# TopPannel.net
KiCad netlist of a schematic drawn in Altium Designer
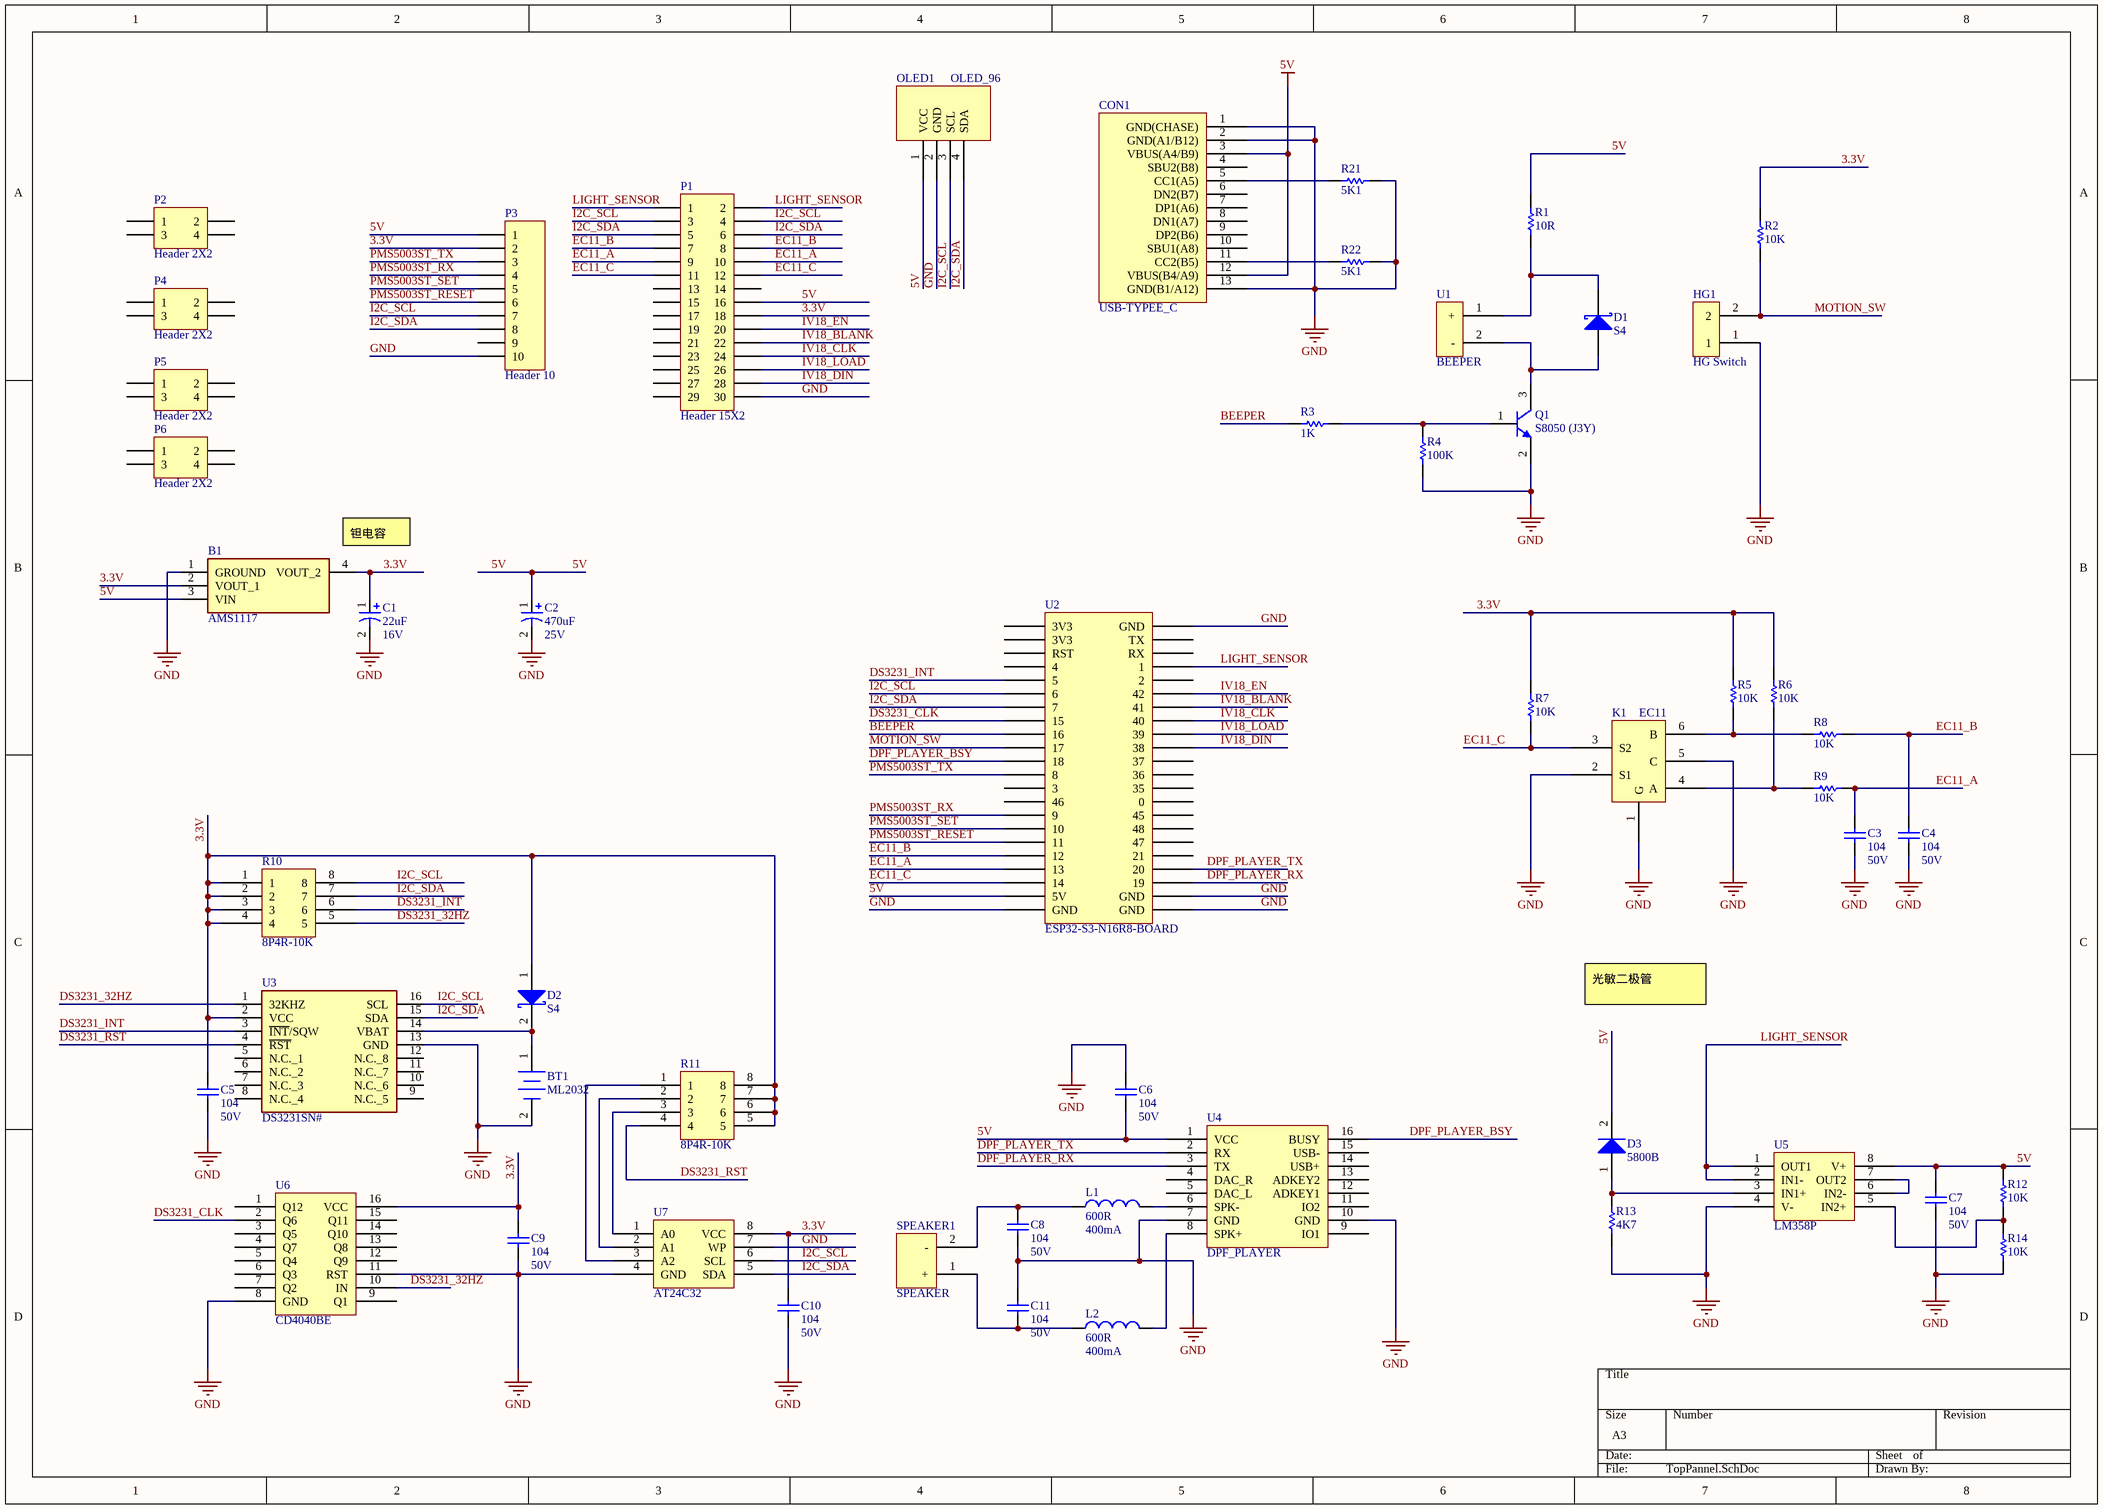
[diagram p0: TopPannel.SchDoc]

(export (version "E")
  (design (tool "Eeschema 10.0.6"))
  (components
    (comp (ref "B1")
      (value "AMS1117")
      (footprint "SOT229P700X180-4N")
      (description "1117")
      (libsource (lib "NeoIVClock") (part "AMS1117"))
    )
    (comp (ref "BT1")
      (value "ML2032")
      (footprint "NeoIVClock:BAT2025-2032-L")
      (description "Multicell Battery")
      (fields (field (name "PUBLISHER") "Altium Limited"))
      (libsource (lib "Miscellaneous Devices") (part "Battery"))
    )
    (comp (ref "C1")
      (value "16V")
      (footprint "NeoIVClock:TC3216-1206")
      (description "Polarized Capacitor (Radial)")
      (fields (field (name "ALTIUM_VALUE") "22uF") (field (name "PUBLISHER") "Altium Limited"))
      (libsource (lib "Miscellaneous Devices") (part "Cap Pol1"))
    )
    (comp (ref "C2")
      (value "25V")
      (footprint "NeoIVClock:SMD-EC-F10")
      (description "Polarized Capacitor (Radial)")
      (fields (field (name "ALTIUM_VALUE") "470uF") (field (name "PUBLISHER") "Altium Limited"))
      (libsource (lib "Miscellaneous Devices") (part "Cap Pol1"))
    )
    (comp (ref "C3")
      (value "50V")
      (footprint "NeoIVClock:CAPC1608L")
      (description "Capacitor")
      (fields (field (name "ALTIUM_VALUE") "104") (field (name "PUBLISHER") "Altium Limited"))
      (libsource (lib "Miscellaneous Devices") (part "Cap"))
    )
    (comp (ref "C4")
      (value "50V")
      (footprint "NeoIVClock:CAPC1608L")
      (description "Capacitor")
      (fields (field (name "ALTIUM_VALUE") "104") (field (name "PUBLISHER") "Altium Limited"))
      (libsource (lib "Miscellaneous Devices") (part "Cap"))
    )
    (comp (ref "C5")
      (value "50V")
      (footprint "NeoIVClock:CAPC1608L")
      (description "Capacitor")
      (fields (field (name "ALTIUM_VALUE") "104") (field (name "PUBLISHER") "Altium Limited"))
      (libsource (lib "Miscellaneous Devices") (part "Cap"))
    )
    (comp (ref "C6")
      (value "50V")
      (footprint "NeoIVClock:CAPC1608L")
      (description "Capacitor")
      (fields (field (name "ALTIUM_VALUE") "104") (field (name "PUBLISHER") "Altium Limited"))
      (libsource (lib "Miscellaneous Devices") (part "Cap"))
    )
    (comp (ref "C7")
      (value "50V")
      (footprint "NeoIVClock:CAPC1608L")
      (description "Capacitor")
      (fields (field (name "ALTIUM_VALUE") "104") (field (name "PUBLISHER") "Altium Limited"))
      (libsource (lib "Miscellaneous Devices") (part "Cap"))
    )
    (comp (ref "C8")
      (value "50V")
      (footprint "NeoIVClock:CAPC1608L")
      (description "Capacitor")
      (fields (field (name "ALTIUM_VALUE") "104") (field (name "PUBLISHER") "Altium Limited"))
      (libsource (lib "Miscellaneous Devices") (part "Cap"))
    )
    (comp (ref "C9")
      (value "50V")
      (footprint "NeoIVClock:CAPC1608L")
      (description "Capacitor")
      (fields (field (name "ALTIUM_VALUE") "104") (field (name "PUBLISHER") "Altium Limited"))
      (libsource (lib "Miscellaneous Devices") (part "Cap"))
    )
    (comp (ref "C10")
      (value "50V")
      (footprint "NeoIVClock:CAPC1608L")
      (description "Capacitor")
      (fields (field (name "ALTIUM_VALUE") "104") (field (name "PUBLISHER") "Altium Limited"))
      (libsource (lib "Miscellaneous Devices") (part "Cap"))
    )
    (comp (ref "C11")
      (value "50V")
      (footprint "NeoIVClock:CAPC1608L")
      (description "Capacitor")
      (fields (field (name "ALTIUM_VALUE") "104") (field (name "PUBLISHER") "Altium Limited"))
      (libsource (lib "Miscellaneous Devices") (part "Cap"))
    )
    (comp (ref "CON1")
      (value "USB-TYPEE_C")
      (footprint "NeoIVClock:USB-TYPE_C")
      (libsource (lib "NeoIVClock") (part "USB-TYPEE_C"))
    )
    (comp (ref "D1")
      (value "S4")
      (footprint "NeoIVClock:CD3216-1206")
      (description "Schottky Diode")
      (fields (field (name "PUBLISHER") "Altium Limited"))
      (libsource (lib "Miscellaneous Devices") (part "D Schottky"))
    )
    (comp (ref "D2")
      (value "S4")
      (footprint "NeoIVClock:CD3216-1206")
      (description "Schottky Diode")
      (fields (field (name "PUBLISHER") "Altium Limited"))
      (libsource (lib "") (part "D Schottky_1"))
    )
    (comp (ref "D3")
      (value "5800B")
      (footprint "NeoIVClock:5800B")
      (description "Default Diode")
      (fields (field (name "PUBLISHER") "Altium Limited"))
      (libsource (lib "Miscellaneous Devices") (part "Diode"))
    )
    (comp (ref "HG1")
      (value "HG Switch")
      (footprint "NeoIVClock:HG")
      (libsource (lib "NeoIVClock") (part "HG"))
    )
    (comp (ref "K1") (value "EC11") (footprint "NeoIVClock:EC11") (libsource (lib "DMI") (part "EC11")))
    (comp (ref "L1")
      (value "400mA")
      (footprint "NeoIVClock:CAPC2012L")
      (description "Inductor")
      (fields (field (name "ALTIUM_VALUE") "600R") (field (name "PUBLISHER") "Altium Limited"))
      (libsource (lib "Miscellaneous Devices") (part "Inductor"))
    )
    (comp (ref "L2")
      (value "400mA")
      (footprint "NeoIVClock:CAPC2012L")
      (description "Inductor")
      (fields (field (name "ALTIUM_VALUE") "600R") (field (name "PUBLISHER") "Altium Limited"))
      (libsource (lib "Miscellaneous Devices") (part "Inductor"))
    )
    (comp (ref "OLED1")
      (value "OLED_96")
      (footprint "NeoIVClock:OLED_96")
      (libsource (lib "NeoIVClock") (part "OLED_96"))
    )
    (comp (ref "P1")
      (value "Header 15X2")
      (footprint "HDR2X15")
      (description "Header, 15-Pin, Dual row")
      (fields (field (name "PUBLISHER") "Altium Limited"))
      (libsource (lib "Miscellaneous Connectors") (part "Header 15X2"))
    )
    (comp (ref "P2")
      (value "Header 2X2")
      (footprint "HDR2X2")
      (description "Header, 2-Pin, Dual row")
      (fields (field (name "PUBLISHER") "Altium Limited"))
      (libsource (lib "Miscellaneous Connectors") (part "Header 2X2"))
    )
    (comp (ref "P3")
      (value "Header 10")
      (footprint "NeoIVClock:XH254-W-10P")
      (description "Header, 10-Pin")
      (fields (field (name "PUBLISHER") "Altium Limited"))
      (libsource (lib "Miscellaneous Connectors") (part "Header 10"))
    )
    (comp (ref "P4")
      (value "Header 2X2")
      (footprint "HDR2X2")
      (description "Header, 2-Pin, Dual row")
      (fields (field (name "PUBLISHER") "Altium Limited"))
      (libsource (lib "Miscellaneous Connectors") (part "Header 2X2"))
    )
    (comp (ref "P5")
      (value "Header 2X2")
      (footprint "HDR2X2")
      (description "Header, 2-Pin, Dual row")
      (fields (field (name "PUBLISHER") "Altium Limited"))
      (libsource (lib "Miscellaneous Connectors") (part "Header 2X2"))
    )
    (comp (ref "P6")
      (value "Header 2X2")
      (footprint "HDR2X2")
      (description "Header, 2-Pin, Dual row")
      (fields (field (name "PUBLISHER") "Altium Limited"))
      (libsource (lib "Miscellaneous Connectors") (part "Header 2X2"))
    )
    (comp (ref "Q1")
      (value "S8050 (J3Y)")
      (footprint "SOT-23B_L")
      (description "NPN Bipolar Transistor")
      (fields (field (name "PUBLISHER") "Altium Limited"))
      (libsource (lib "Miscellaneous Devices") (part "NPN"))
    )
    (comp (ref "R1")
      (value "10R")
      (footprint "NeoIVClock:RESC1608L")
      (description "Resistor")
      (fields (field (name "Comment") "Res1") (field (name "PUBLISHER") "Altium Limited"))
      (libsource (lib "Miscellaneous Devices") (part "Res1"))
    )
    (comp (ref "R2")
      (value "10K")
      (footprint "NeoIVClock:RESC1608L")
      (description "Resistor")
      (fields (field (name "Comment") "Res1") (field (name "PUBLISHER") "Altium Limited"))
      (libsource (lib "Miscellaneous Devices") (part "Res1"))
    )
    (comp (ref "R3")
      (value "1K")
      (footprint "NeoIVClock:RESC1608L")
      (description "Resistor")
      (fields (field (name "Comment") "Res1") (field (name "PUBLISHER") "Altium Limited"))
      (libsource (lib "Miscellaneous Devices") (part "Res1"))
    )
    (comp (ref "R4")
      (value "100K")
      (footprint "NeoIVClock:RESC1608L")
      (description "Resistor")
      (fields (field (name "Comment") "Res1") (field (name "PUBLISHER") "Altium Limited"))
      (libsource (lib "Miscellaneous Devices") (part "Res1"))
    )
    (comp (ref "R5")
      (value "10K")
      (footprint "NeoIVClock:RESC1608L")
      (description "Resistor")
      (fields (field (name "Comment") "Res1") (field (name "PUBLISHER") "Altium Limited"))
      (libsource (lib "Miscellaneous Devices") (part "Res1"))
    )
    (comp (ref "R6")
      (value "10K")
      (footprint "NeoIVClock:RESC1608L")
      (description "Resistor")
      (fields (field (name "Comment") "Res1") (field (name "PUBLISHER") "Altium Limited"))
      (libsource (lib "Miscellaneous Devices") (part "Res1"))
    )
    (comp (ref "R7")
      (value "10K")
      (footprint "NeoIVClock:RESC1608L")
      (description "Resistor")
      (fields (field (name "Comment") "Res1") (field (name "PUBLISHER") "Altium Limited"))
      (libsource (lib "Miscellaneous Devices") (part "Res1"))
    )
    (comp (ref "R8")
      (value "10K")
      (footprint "NeoIVClock:RESC1608L")
      (description "Resistor")
      (fields (field (name "Comment") "Res1") (field (name "PUBLISHER") "Altium Limited"))
      (libsource (lib "Miscellaneous Devices") (part "Res1"))
    )
    (comp (ref "R9")
      (value "10K")
      (footprint "NeoIVClock:RESC1608L")
      (description "Resistor")
      (fields (field (name "Comment") "Res1") (field (name "PUBLISHER") "Altium Limited"))
      (libsource (lib "Miscellaneous Devices") (part "Res1"))
    )
    (comp (ref "R10") (value "8P4R-10K") (footprint "8P4R 0603") (libsource (lib "NeoIVClock") (part "8P4R")))
    (comp (ref "R11")
      (value "8P4R-10K")
      (footprint "NeoIVClock:8P4R 0603")
      (libsource (lib "NeoIVClock") (part "8P4R"))
    )
    (comp (ref "R12")
      (value "10K")
      (footprint "NeoIVClock:RESC1608L")
      (description "Resistor")
      (fields (field (name "Comment") "Res1") (field (name "PUBLISHER") "Altium Limited"))
      (libsource (lib "Miscellaneous Devices") (part "Res1"))
    )
    (comp (ref "R13")
      (value "4K7")
      (footprint "NeoIVClock:RESC1608L")
      (description "Resistor")
      (fields (field (name "Comment") "Res1") (field (name "PUBLISHER") "Altium Limited"))
      (libsource (lib "Miscellaneous Devices") (part "Res1"))
    )
    (comp (ref "R14")
      (value "10K")
      (footprint "NeoIVClock:RESC1608L")
      (description "Resistor")
      (fields (field (name "Comment") "Res1") (field (name "PUBLISHER") "Altium Limited"))
      (libsource (lib "Miscellaneous Devices") (part "Res1"))
    )
    (comp (ref "R21")
      (value "5K1")
      (footprint "NeoIVClock:RESC1608L")
      (description "Resistor")
      (fields (field (name "Comment") "Res1") (field (name "PUBLISHER") "Altium Limited"))
      (libsource (lib "Miscellaneous Devices") (part "Res1"))
    )
    (comp (ref "R22")
      (value "5K1")
      (footprint "NeoIVClock:RESC1608L")
      (description "Resistor")
      (fields (field (name "Comment") "Res1") (field (name "PUBLISHER") "Altium Limited"))
      (libsource (lib "Miscellaneous Devices") (part "Res1"))
    )
    (comp (ref "SPEAKER1")
      (value "SPEAKER")
      (footprint "NeoIVClock:SPEAKER")
      (libsource (lib "NeoIVClock") (part "SPEAKER"))
    )
    (comp (ref "U1")
      (value "BEEPER")
      (footprint "NeoIVClock:BEEPER")
      (libsource (lib "NeoIVClock") (part "BEEPER"))
    )
    (comp (ref "U2")
      (value "ESP32-S3-N16R8-BOARD")
      (footprint "NeoIVClock:ESP32-S3-N16R8-BOARD")
      (libsource (lib "NeoIVClock") (part "ESP32-S3-N16R8-BOARD"))
    )
    (comp (ref "U3")
      (value "DS3231SN#")
      (footprint "NeoIVClock:SOIC127P1032X265-16N")
      (fields (field (name "MOUSER PART NUMBER") "700-DS3231SN#"))
      (libsource (lib "NeoIVClock") (part "DS3231SN#"))
    )
    (comp (ref "U4")
      (value "DPF_PLAYER")
      (footprint "NeoIVClock:DPF_PLAYER")
      (libsource (lib "NeoIVClock") (part "DPF_PLAYER"))
    )
    (comp (ref "U5") (value "LM358P") (footprint "DIP-8") (libsource (lib "NeoIVClock") (part "LM358P")))
    (comp (ref "U6")
      (value "CD4040BE")
      (footprint "NeoIVClock:DIP-16")
      (libsource (lib "NeoIVClock") (part "CD4040BE"))
    )
    (comp (ref "U7")
      (value "AT24C32")
      (footprint "NeoIVClock:DIP-8")
      (libsource (lib "NeoIVClock") (part "AT24C32"))
    )
  )
  (nets
    (net (code "1") (name "/3.3V") (class "Default")
      (node (ref "B1") (pin "2") (pinfunction "VOUT_1_2") (pintype "passive"))
      (node (ref "B1") (pin "4") (pinfunction "VOUT_2_4") (pintype "passive"))
      (node (ref "C1") (pin "1") (pinfunction "1_1") (pintype "passive"))
      (node (ref "C10") (pin "2") (pinfunction "2_2") (pintype "passive"))
      (node (ref "C5") (pin "2") (pinfunction "2_2") (pintype "passive"))
      (node (ref "C9") (pin "2") (pinfunction "2_2") (pintype "passive"))
      (node (ref "D2") (pin "1") (pinfunction "A_1") (pintype "passive"))
      (node (ref "P1") (pin "18") (pinfunction "18_18") (pintype "passive"))
      (node (ref "P3") (pin "2") (pinfunction "2_2") (pintype "passive"))
      (node (ref "R10") (pin "1") (pinfunction "1_1") (pintype "passive"))
      (node (ref "R10") (pin "2") (pinfunction "2_2") (pintype "passive"))
      (node (ref "R10") (pin "3") (pinfunction "3_3") (pintype "passive"))
      (node (ref "R10") (pin "4") (pinfunction "4_4") (pintype "passive"))
      (node (ref "R11") (pin "5") (pinfunction "5_5") (pintype "passive"))
      (node (ref "R11") (pin "6") (pinfunction "6_6") (pintype "passive"))
      (node (ref "R11") (pin "7") (pinfunction "7_7") (pintype "passive"))
      (node (ref "R11") (pin "8") (pinfunction "8_8") (pintype "passive"))
      (node (ref "R2") (pin "1") (pinfunction "1_1") (pintype "passive"))
      (node (ref "R5") (pin "1") (pinfunction "1_1") (pintype "passive"))
      (node (ref "R6") (pin "1") (pinfunction "1_1") (pintype "passive"))
      (node (ref "R7") (pin "1") (pinfunction "1_1") (pintype "passive"))
      (node (ref "U3") (pin "2") (pinfunction "VCC_2") (pintype "passive"))
      (node (ref "U6") (pin "16") (pinfunction "VCC_16") (pintype "passive"))
      (node (ref "U7") (pin "8") (pinfunction "VCC_8") (pintype "passive"))
    )
    (net (code "2") (name "/BEEPER") (class "Default")
      (node (ref "R3") (pin "1") (pinfunction "1_1") (pintype "passive"))
      (node (ref "U2") (pin "9") (pinfunction "16_9") (pintype "passive"))
    )
    (net (code "3") (name "/DPF_PLAYER_BSY") (class "Default")
      (node (ref "U2") (pin "11") (pinfunction "18_11") (pintype "passive"))
      (node (ref "U4") (pin "16") (pinfunction "BUSY_16") (pintype "passive"))
    )
    (net (code "4") (name "/DPF_PLAYER_RX") (class "Default")
      (node (ref "U2") (pin "25") (pinfunction "19_25") (pintype "passive"))
      (node (ref "U4") (pin "3") (pinfunction "TX_3") (pintype "passive"))
    )
    (net (code "5") (name "/DPF_PLAYER_TX") (class "Default")
      (node (ref "U2") (pin "26") (pinfunction "20_26") (pintype "passive"))
      (node (ref "U4") (pin "2") (pinfunction "RX_2") (pintype "passive"))
    )
    (net (code "6") (name "/DS3231_32HZ") (class "Default")
      (node (ref "R10") (pin "5") (pinfunction "5_5") (pintype "passive"))
      (node (ref "U3") (pin "1") (pinfunction "32KHZ_1") (pintype "passive"))
      (node (ref "U6") (pin "10") (pinfunction "IN_10") (pintype "passive"))
    )
    (net (code "7") (name "/DS3231_CLK") (class "Default")
      (node (ref "U2") (pin "8") (pinfunction "15_8") (pintype "passive"))
      (node (ref "U6") (pin "2") (pinfunction "Q6_2") (pintype "passive"))
    )
    (net (code "8") (name "/DS3231_INT") (class "Default")
      (node (ref "R10") (pin "6") (pinfunction "6_6") (pintype "passive"))
      (node (ref "U2") (pin "5") (pinfunction "5_5") (pintype "passive"))
      (node (ref "U3") (pin "3") (pinfunction "~{INT}/SQW_3") (pintype "passive"))
    )
    (net (code "9") (name "/DS3231_RST") (class "Default")
      (node (ref "R11") (pin "4") (pinfunction "4_4") (pintype "passive"))
      (node (ref "U3") (pin "4") (pinfunction "~{RST}_4") (pintype "passive"))
    )
    (net (code "10") (name "/EC11_A") (class "Default")
      (node (ref "C3") (pin "2") (pinfunction "2_2") (pintype "passive"))
      (node (ref "P1") (pin "10") (pinfunction "10_10") (pintype "passive"))
      (node (ref "P1") (pin "9") (pinfunction "9_9") (pintype "passive"))
      (node (ref "R9") (pin "2") (pinfunction "2_2") (pintype "passive"))
      (node (ref "U2") (pin "19") (pinfunction "13_19") (pintype "passive"))
    )
    (net (code "11") (name "/EC11_B") (class "Default")
      (node (ref "C4") (pin "2") (pinfunction "2_2") (pintype "passive"))
      (node (ref "P1") (pin "7") (pinfunction "7_7") (pintype "passive"))
      (node (ref "P1") (pin "8") (pinfunction "8_8") (pintype "passive"))
      (node (ref "R8") (pin "2") (pinfunction "2_2") (pintype "passive"))
      (node (ref "U2") (pin "18") (pinfunction "12_18") (pintype "passive"))
    )
    (net (code "12") (name "/EC11_C") (class "Default")
      (node (ref "K1") (pin "3") (pinfunction "S2_3") (pintype "passive"))
      (node (ref "P1") (pin "11") (pinfunction "11_11") (pintype "passive"))
      (node (ref "P1") (pin "12") (pinfunction "12_12") (pintype "passive"))
      (node (ref "R7") (pin "2") (pinfunction "2_2") (pintype "passive"))
      (node (ref "U2") (pin "20") (pinfunction "14_20") (pintype "passive"))
    )
    (net (code "13") (name "/I2C_SCL") (class "Default")
      (node (ref "OLED1") (pin "3") (pinfunction "SCL_3") (pintype "passive"))
      (node (ref "P1") (pin "3") (pinfunction "3_3") (pintype "passive"))
      (node (ref "P1") (pin "4") (pinfunction "4_4") (pintype "passive"))
      (node (ref "P3") (pin "7") (pinfunction "7_7") (pintype "passive"))
      (node (ref "R10") (pin "8") (pinfunction "8_8") (pintype "passive"))
      (node (ref "U2") (pin "6") (pinfunction "6_6") (pintype "passive"))
      (node (ref "U3") (pin "16") (pinfunction "SCL_16") (pintype "passive"))
      (node (ref "U7") (pin "6") (pinfunction "SCL_6") (pintype "passive"))
    )
    (net (code "14") (name "/I2C_SDA") (class "Default")
      (node (ref "OLED1") (pin "4") (pinfunction "SDA_4") (pintype "passive"))
      (node (ref "P1") (pin "5") (pinfunction "5_5") (pintype "passive"))
      (node (ref "P1") (pin "6") (pinfunction "6_6") (pintype "passive"))
      (node (ref "P3") (pin "8") (pinfunction "8_8") (pintype "passive"))
      (node (ref "R10") (pin "7") (pinfunction "7_7") (pintype "passive"))
      (node (ref "U2") (pin "7") (pinfunction "7_7") (pintype "passive"))
      (node (ref "U3") (pin "15") (pinfunction "SDA_15") (pintype "passive"))
      (node (ref "U7") (pin "5") (pinfunction "SDA_5") (pintype "passive"))
    )
    (net (code "15") (name "/IV18_BLANK") (class "Default")
      (node (ref "P1") (pin "22") (pinfunction "22_22") (pintype "passive"))
      (node (ref "U2") (pin "38") (pinfunction "41_38") (pintype "passive"))
    )
    (net (code "16") (name "/IV18_CLK") (class "Default")
      (node (ref "P1") (pin "24") (pinfunction "24_24") (pintype "passive"))
      (node (ref "U2") (pin "37") (pinfunction "40_37") (pintype "passive"))
    )
    (net (code "17") (name "/IV18_DIN") (class "Default")
      (node (ref "P1") (pin "28") (pinfunction "28_28") (pintype "passive"))
      (node (ref "U2") (pin "35") (pinfunction "38_35") (pintype "passive"))
    )
    (net (code "18") (name "/IV18_EN") (class "Default")
      (node (ref "P1") (pin "20") (pinfunction "20_20") (pintype "passive"))
      (node (ref "U2") (pin "39") (pinfunction "42_39") (pintype "passive"))
    )
    (net (code "19") (name "/IV18_LOAD") (class "Default")
      (node (ref "P1") (pin "26") (pinfunction "26_26") (pintype "passive"))
      (node (ref "U2") (pin "36") (pinfunction "39_36") (pintype "passive"))
    )
    (net (code "20") (name "/LIGHT_SENSOR") (class "Default")
      (node (ref "P1") (pin "1") (pinfunction "1_1") (pintype "passive"))
      (node (ref "P1") (pin "2") (pinfunction "2_2") (pintype "passive"))
      (node (ref "U2") (pin "41") (pinfunction "1_41") (pintype "passive"))
      (node (ref "U5") (pin "1") (pinfunction "OUT1_1") (pintype "passive"))
      (node (ref "U5") (pin "2") (pinfunction "IN1-_2") (pintype "passive"))
    )
    (net (code "21") (name "/MOTION_SW") (class "Default")
      (node (ref "HG1") (pin "2") (pinfunction "2_2") (pintype "passive"))
      (node (ref "R2") (pin "2") (pinfunction "2_2") (pintype "passive"))
      (node (ref "U2") (pin "10") (pinfunction "17_10") (pintype "passive"))
    )
    (net (code "22") (name "/PMS5003ST_RESET") (class "Default")
      (node (ref "P3") (pin "6") (pinfunction "6_6") (pintype "passive"))
      (node (ref "U2") (pin "17") (pinfunction "11_17") (pintype "passive"))
    )
    (net (code "23") (name "/PMS5003ST_RX") (class "Default")
      (node (ref "P3") (pin "4") (pinfunction "4_4") (pintype "passive"))
      (node (ref "U2") (pin "15") (pinfunction "9_15") (pintype "passive"))
    )
    (net (code "24") (name "/PMS5003ST_SET") (class "Default")
      (node (ref "P3") (pin "5") (pinfunction "5_5") (pintype "passive"))
      (node (ref "U2") (pin "16") (pinfunction "10_16") (pintype "passive"))
    )
    (net (code "25") (name "/PMS5003ST_TX") (class "Default")
      (node (ref "P3") (pin "3") (pinfunction "3_3") (pintype "passive"))
      (node (ref "U2") (pin "12") (pinfunction "8_12") (pintype "passive"))
    )
    (net (code "26") (name "5V") (class "Default")
      (node (ref "B1") (pin "3") (pinfunction "VIN_3") (pintype "passive"))
      (node (ref "C2") (pin "1") (pinfunction "1_1") (pintype "passive"))
      (node (ref "C6") (pin "1") (pinfunction "1_1") (pintype "passive"))
      (node (ref "C7") (pin "2") (pinfunction "2_2") (pintype "passive"))
      (node (ref "CON1") (pin "12") (pinfunction "VBUS(B4/A9)_12") (pintype "passive"))
      (node (ref "CON1") (pin "3") (pinfunction "VBUS(A4/B9)_3") (pintype "passive"))
      (node (ref "D3") (pin "2") (pinfunction "K_2") (pintype "passive"))
      (node (ref "OLED1") (pin "1") (pinfunction "VCC_1") (pintype "passive"))
      (node (ref "P1") (pin "16") (pinfunction "16_16") (pintype "passive"))
      (node (ref "P3") (pin "1") (pinfunction "1_1") (pintype "passive"))
      (node (ref "R1") (pin "1") (pinfunction "1_1") (pintype "passive"))
      (node (ref "R12") (pin "1") (pinfunction "1_1") (pintype "passive"))
      (node (ref "U2") (pin "21") (pinfunction "5V_21") (pintype "passive"))
      (node (ref "U4") (pin "1") (pinfunction "VCC_1") (pintype "passive"))
      (node (ref "U5") (pin "8") (pinfunction "V+_8") (pintype "passive"))
    )
    (net (code "27") (name "GND") (class "Default")
      (node (ref "B1") (pin "1") (pinfunction "GROUND_1") (pintype "passive"))
      (node (ref "BT1") (pin "2") (pinfunction "-_2") (pintype "passive"))
      (node (ref "C1") (pin "2") (pinfunction "2_2") (pintype "passive"))
      (node (ref "C10") (pin "1") (pinfunction "1_1") (pintype "passive"))
      (node (ref "C11") (pin "2") (pinfunction "2_2") (pintype "passive"))
      (node (ref "C2") (pin "2") (pinfunction "2_2") (pintype "passive"))
      (node (ref "C3") (pin "1") (pinfunction "1_1") (pintype "passive"))
      (node (ref "C4") (pin "1") (pinfunction "1_1") (pintype "passive"))
      (node (ref "C5") (pin "1") (pinfunction "1_1") (pintype "passive"))
      (node (ref "C6") (pin "2") (pinfunction "2_2") (pintype "passive"))
      (node (ref "C7") (pin "1") (pinfunction "1_1") (pintype "passive"))
      (node (ref "C8") (pin "1") (pinfunction "1_1") (pintype "passive"))
      (node (ref "C9") (pin "1") (pinfunction "1_1") (pintype "passive"))
      (node (ref "CON1") (pin "1") (pinfunction "GND(CHASE)_1") (pintype "passive"))
      (node (ref "CON1") (pin "13") (pinfunction "GND(B1/A12)_13") (pintype "passive"))
      (node (ref "CON1") (pin "2") (pinfunction "GND(A1/B12)_2") (pintype "passive"))
      (node (ref "HG1") (pin "1") (pinfunction "1_1") (pintype "passive"))
      (node (ref "K1") (pin "1") (pinfunction "G_1") (pintype "passive"))
      (node (ref "K1") (pin "2") (pinfunction "S1_2") (pintype "passive"))
      (node (ref "K1") (pin "5") (pinfunction "C_5") (pintype "passive"))
      (node (ref "OLED1") (pin "2") (pinfunction "GND_2") (pintype "passive"))
      (node (ref "P1") (pin "30") (pinfunction "30_30") (pintype "passive"))
      (node (ref "P3") (pin "10") (pinfunction "10_10") (pintype "passive"))
      (node (ref "Q1") (pin "2") (pinfunction "E_2") (pintype "passive"))
      (node (ref "R13") (pin "2") (pinfunction "2_2") (pintype "passive"))
      (node (ref "R14") (pin "2") (pinfunction "2_2") (pintype "passive"))
      (node (ref "R21") (pin "2") (pinfunction "2_2") (pintype "passive"))
      (node (ref "R22") (pin "2") (pinfunction "2_2") (pintype "passive"))
      (node (ref "R4") (pin "2") (pinfunction "2_2") (pintype "passive"))
      (node (ref "U2") (pin "22") (pinfunction "GND_22") (pintype "passive"))
      (node (ref "U2") (pin "23") (pinfunction "GND_23") (pintype "passive"))
      (node (ref "U2") (pin "24") (pinfunction "GND_24") (pintype "passive"))
      (node (ref "U2") (pin "44") (pinfunction "GND_44") (pintype "passive"))
      (node (ref "U3") (pin "13") (pinfunction "GND_13") (pintype "passive"))
      (node (ref "U4") (pin "10") (pinfunction "GND_10") (pintype "passive"))
      (node (ref "U4") (pin "7") (pinfunction "GND_7") (pintype "passive"))
      (node (ref "U5") (pin "4") (pinfunction "V-_4") (pintype "passive"))
      (node (ref "U6") (pin "11") (pinfunction "RST_11") (pintype "passive"))
      (node (ref "U6") (pin "8") (pinfunction "GND_8") (pintype "passive"))
      (node (ref "U7") (pin "4") (pinfunction "GND_4") (pintype "passive"))
      (node (ref "U7") (pin "7") (pinfunction "WP_7") (pintype "passive"))
    )
    (net (code "28") (name "Net-(BT1-+)") (class "Default")
      (node (ref "BT1") (pin "1") (pinfunction "+_1") (pintype "passive"))
      (node (ref "D2") (pin "2") (pinfunction "K_2") (pintype "passive"))
      (node (ref "U3") (pin "14") (pinfunction "VBAT_14") (pintype "passive"))
    )
    (net (code "29") (name "Net-(CON1-CC1(A5))") (class "Default")
      (node (ref "CON1") (pin "5") (pinfunction "CC1(A5)_5") (pintype "passive"))
      (node (ref "R21") (pin "1") (pinfunction "1_1") (pintype "passive"))
    )
    (net (code "30") (name "Net-(CON1-CC2(B5))") (class "Default")
      (node (ref "CON1") (pin "11") (pinfunction "CC2(B5)_11") (pintype "passive"))
      (node (ref "R22") (pin "1") (pinfunction "1_1") (pintype "passive"))
    )
    (net (code "31") (name "Net-(D1-A)") (class "Default")
      (node (ref "D1") (pin "1") (pinfunction "A_1") (pintype "passive"))
      (node (ref "Q1") (pin "3") (pinfunction "C_3") (pintype "passive"))
      (node (ref "U1") (pin "2") (pinfunction "-_2") (pintype "passive"))
    )
    (net (code "32") (name "Net-(D1-K)") (class "Default")
      (node (ref "D1") (pin "2") (pinfunction "K_2") (pintype "passive"))
      (node (ref "R1") (pin "2") (pinfunction "2_2") (pintype "passive"))
      (node (ref "U1") (pin "1") (pinfunction "+_1") (pintype "passive"))
    )
    (net (code "33") (name "Net-(D3-A)") (class "Default")
      (node (ref "D3") (pin "1") (pinfunction "A_1") (pintype "passive"))
      (node (ref "R13") (pin "1") (pinfunction "1_1") (pintype "passive"))
      (node (ref "U5") (pin "3") (pinfunction "IN1+_3") (pintype "passive"))
    )
    (net (code "34") (name "Net-(K1-A)") (class "Default")
      (node (ref "K1") (pin "4") (pinfunction "A_4") (pintype "passive"))
      (node (ref "R6") (pin "2") (pinfunction "2_2") (pintype "passive"))
      (node (ref "R9") (pin "1") (pinfunction "1_1") (pintype "passive"))
    )
    (net (code "35") (name "Net-(K1-B)") (class "Default")
      (node (ref "K1") (pin "6") (pinfunction "B_6") (pintype "passive"))
      (node (ref "R5") (pin "2") (pinfunction "2_2") (pintype "passive"))
      (node (ref "R8") (pin "1") (pinfunction "1_1") (pintype "passive"))
    )
    (net (code "36") (name "Net-(Q1-B)") (class "Default")
      (node (ref "Q1") (pin "1") (pinfunction "B_1") (pintype "passive"))
      (node (ref "R3") (pin "2") (pinfunction "2_2") (pintype "passive"))
      (node (ref "R4") (pin "1") (pinfunction "1_1") (pintype "passive"))
    )
    (net (code "37") (name "Net-(SPEAKER1-+)") (class "Default")
      (node (ref "C11") (pin "1") (pinfunction "1_1") (pintype "passive"))
      (node (ref "L2") (pin "1") (pinfunction "1_1") (pintype "passive"))
      (node (ref "SPEAKER1") (pin "1") (pinfunction "+_1") (pintype "passive"))
    )
    (net (code "38") (name "Net-(SPEAKER1--)") (class "Default")
      (node (ref "C8") (pin "2") (pinfunction "2_2") (pintype "passive"))
      (node (ref "L1") (pin "1") (pinfunction "1_1") (pintype "passive"))
      (node (ref "SPEAKER1") (pin "2") (pinfunction "-_2") (pintype "passive"))
    )
    (net (code "39") (name "Net-(U4-SPK+)") (class "Default")
      (node (ref "L2") (pin "2") (pinfunction "2_2") (pintype "passive"))
      (node (ref "U4") (pin "8") (pinfunction "SPK+_8") (pintype "passive"))
    )
    (net (code "40") (name "Net-(U4-SPK-)") (class "Default")
      (node (ref "L1") (pin "2") (pinfunction "2_2") (pintype "passive"))
      (node (ref "U4") (pin "6") (pinfunction "SPK-_6") (pintype "passive"))
    )
    (net (code "41") (name "Net-(U5-IN2+)") (class "Default")
      (node (ref "R12") (pin "2") (pinfunction "2_2") (pintype "passive"))
      (node (ref "R14") (pin "1") (pinfunction "1_1") (pintype "passive"))
      (node (ref "U5") (pin "5") (pinfunction "IN2+_5") (pintype "passive"))
    )
    (net (code "42") (name "Net-(U5-IN2-)") (class "Default")
      (node (ref "U5") (pin "6") (pinfunction "IN2-_6") (pintype "passive"))
      (node (ref "U5") (pin "7") (pinfunction "OUT2_7") (pintype "passive"))
    )
    (net (code "43") (name "Net-(U7-A0)") (class "Default")
      (node (ref "R11") (pin "3") (pinfunction "3_3") (pintype "passive"))
      (node (ref "U7") (pin "1") (pinfunction "A0_1") (pintype "passive"))
    )
    (net (code "44") (name "Net-(U7-A1)") (class "Default")
      (node (ref "R11") (pin "2") (pinfunction "2_2") (pintype "passive"))
      (node (ref "U7") (pin "2") (pinfunction "A1_2") (pintype "passive"))
    )
    (net (code "45") (name "Net-(U7-A2)") (class "Default")
      (node (ref "R11") (pin "1") (pinfunction "1_1") (pintype "passive"))
      (node (ref "U7") (pin "3") (pinfunction "A2_3") (pintype "passive"))
    )
    (net (code "46") (name "unconnected-(CON1-DN1(A7)-Pad8)") (class "Default")
      (node (ref "CON1") (pin "8") (pinfunction "DN1(A7)_8") (pintype "passive"))
    )
    (net (code "47") (name "unconnected-(CON1-DN2(B7)-Pad6)") (class "Default")
      (node (ref "CON1") (pin "6") (pinfunction "DN2(B7)_6") (pintype "passive"))
    )
    (net (code "48") (name "unconnected-(CON1-DP1(A6)-Pad7)") (class "Default")
      (node (ref "CON1") (pin "7") (pinfunction "DP1(A6)_7") (pintype "passive"))
    )
    (net (code "49") (name "unconnected-(CON1-DP2(B6)-Pad9)") (class "Default")
      (node (ref "CON1") (pin "9") (pinfunction "DP2(B6)_9") (pintype "passive"))
    )
    (net (code "50") (name "unconnected-(CON1-SBU1(A8)-Pad10)") (class "Default")
      (node (ref "CON1") (pin "10") (pinfunction "SBU1(A8)_10") (pintype "passive"))
    )
    (net (code "51") (name "unconnected-(CON1-SBU2(B8)-Pad4)") (class "Default")
      (node (ref "CON1") (pin "4") (pinfunction "SBU2(B8)_4") (pintype "passive"))
    )
    (net (code "52") (name "unconnected-(P1-Pad13)") (class "Default")
      (node (ref "P1") (pin "13") (pinfunction "13_13") (pintype "passive"))
    )
    (net (code "53") (name "unconnected-(P1-Pad14)") (class "Default")
      (node (ref "P1") (pin "14") (pinfunction "14_14") (pintype "passive"))
    )
    (net (code "54") (name "unconnected-(P1-Pad15)") (class "Default")
      (node (ref "P1") (pin "15") (pinfunction "15_15") (pintype "passive"))
    )
    (net (code "55") (name "unconnected-(P1-Pad17)") (class "Default")
      (node (ref "P1") (pin "17") (pinfunction "17_17") (pintype "passive"))
    )
    (net (code "56") (name "unconnected-(P1-Pad19)") (class "Default")
      (node (ref "P1") (pin "19") (pinfunction "19_19") (pintype "passive"))
    )
    (net (code "57") (name "unconnected-(P1-Pad21)") (class "Default")
      (node (ref "P1") (pin "21") (pinfunction "21_21") (pintype "passive"))
    )
    (net (code "58") (name "unconnected-(P1-Pad23)") (class "Default")
      (node (ref "P1") (pin "23") (pinfunction "23_23") (pintype "passive"))
    )
    (net (code "59") (name "unconnected-(P1-Pad25)") (class "Default")
      (node (ref "P1") (pin "25") (pinfunction "25_25") (pintype "passive"))
    )
    (net (code "60") (name "unconnected-(P1-Pad27)") (class "Default")
      (node (ref "P1") (pin "27") (pinfunction "27_27") (pintype "passive"))
    )
    (net (code "61") (name "unconnected-(P1-Pad29)") (class "Default")
      (node (ref "P1") (pin "29") (pinfunction "29_29") (pintype "passive"))
    )
    (net (code "62") (name "unconnected-(P2-Pad1)") (class "Default")
      (node (ref "P2") (pin "1") (pinfunction "1_1") (pintype "passive"))
    )
    (net (code "63") (name "unconnected-(P2-Pad2)") (class "Default")
      (node (ref "P2") (pin "2") (pinfunction "2_2") (pintype "passive"))
    )
    (net (code "64") (name "unconnected-(P2-Pad3)") (class "Default")
      (node (ref "P2") (pin "3") (pinfunction "3_3") (pintype "passive"))
    )
    (net (code "65") (name "unconnected-(P2-Pad4)") (class "Default")
      (node (ref "P2") (pin "4") (pinfunction "4_4") (pintype "passive"))
    )
    (net (code "66") (name "unconnected-(P3-Pad9)") (class "Default")
      (node (ref "P3") (pin "9") (pinfunction "9_9") (pintype "passive"))
    )
    (net (code "67") (name "unconnected-(P4-Pad1)") (class "Default")
      (node (ref "P4") (pin "1") (pinfunction "1_1") (pintype "passive"))
    )
    (net (code "68") (name "unconnected-(P4-Pad2)") (class "Default")
      (node (ref "P4") (pin "2") (pinfunction "2_2") (pintype "passive"))
    )
    (net (code "69") (name "unconnected-(P4-Pad3)") (class "Default")
      (node (ref "P4") (pin "3") (pinfunction "3_3") (pintype "passive"))
    )
    (net (code "70") (name "unconnected-(P4-Pad4)") (class "Default")
      (node (ref "P4") (pin "4") (pinfunction "4_4") (pintype "passive"))
    )
    (net (code "71") (name "unconnected-(P5-Pad1)") (class "Default")
      (node (ref "P5") (pin "1") (pinfunction "1_1") (pintype "passive"))
    )
    (net (code "72") (name "unconnected-(P5-Pad2)") (class "Default")
      (node (ref "P5") (pin "2") (pinfunction "2_2") (pintype "passive"))
    )
    (net (code "73") (name "unconnected-(P5-Pad3)") (class "Default")
      (node (ref "P5") (pin "3") (pinfunction "3_3") (pintype "passive"))
    )
    (net (code "74") (name "unconnected-(P5-Pad4)") (class "Default")
      (node (ref "P5") (pin "4") (pinfunction "4_4") (pintype "passive"))
    )
    (net (code "75") (name "unconnected-(P6-Pad1)") (class "Default")
      (node (ref "P6") (pin "1") (pinfunction "1_1") (pintype "passive"))
    )
    (net (code "76") (name "unconnected-(P6-Pad2)") (class "Default")
      (node (ref "P6") (pin "2") (pinfunction "2_2") (pintype "passive"))
    )
    (net (code "77") (name "unconnected-(P6-Pad3)") (class "Default")
      (node (ref "P6") (pin "3") (pinfunction "3_3") (pintype "passive"))
    )
    (net (code "78") (name "unconnected-(P6-Pad4)") (class "Default")
      (node (ref "P6") (pin "4") (pinfunction "4_4") (pintype "passive"))
    )
    (net (code "79") (name "unconnected-(U2-0-Pad31)") (class "Default")
      (node (ref "U2") (pin "31") (pinfunction "0_31") (pintype "passive"))
    )
    (net (code "80") (name "unconnected-(U2-2-Pad40)") (class "Default")
      (node (ref "U2") (pin "40") (pinfunction "2_40") (pintype "passive"))
    )
    (net (code "81") (name "unconnected-(U2-3-Pad13)") (class "Default")
      (node (ref "U2") (pin "13") (pinfunction "3_13") (pintype "passive"))
    )
    (net (code "82") (name "unconnected-(U2-3V3-Pad1)") (class "Default")
      (node (ref "U2") (pin "1") (pinfunction "3V3_1") (pintype "passive"))
    )
    (net (code "83") (name "unconnected-(U2-3V3-Pad2)") (class "Default")
      (node (ref "U2") (pin "2") (pinfunction "3V3_2") (pintype "passive"))
    )
    (net (code "84") (name "unconnected-(U2-21-Pad27)") (class "Default")
      (node (ref "U2") (pin "27") (pinfunction "21_27") (pintype "passive"))
    )
    (net (code "85") (name "unconnected-(U2-35-Pad32)") (class "Default")
      (node (ref "U2") (pin "32") (pinfunction "35_32") (pintype "passive"))
    )
    (net (code "86") (name "unconnected-(U2-36-Pad33)") (class "Default")
      (node (ref "U2") (pin "33") (pinfunction "36_33") (pintype "passive"))
    )
    (net (code "87") (name "unconnected-(U2-37-Pad34)") (class "Default")
      (node (ref "U2") (pin "34") (pinfunction "37_34") (pintype "passive"))
    )
    (net (code "88") (name "unconnected-(U2-45-Pad30)") (class "Default")
      (node (ref "U2") (pin "30") (pinfunction "45_30") (pintype "passive"))
    )
    (net (code "89") (name "unconnected-(U2-46-Pad14)") (class "Default")
      (node (ref "U2") (pin "14") (pinfunction "46_14") (pintype "passive"))
    )
    (net (code "90") (name "unconnected-(U2-47-Pad28)") (class "Default")
      (node (ref "U2") (pin "28") (pinfunction "47_28") (pintype "passive"))
    )
    (net (code "91") (name "unconnected-(U2-48-Pad29)") (class "Default")
      (node (ref "U2") (pin "29") (pinfunction "48_29") (pintype "passive"))
    )
    (net (code "92") (name "unconnected-(U2-Pad4)") (class "Default")
      (node (ref "U2") (pin "4") (pinfunction "4_4") (pintype "passive"))
    )
    (net (code "93") (name "unconnected-(U2-RST-Pad3)") (class "Default")
      (node (ref "U2") (pin "3") (pinfunction "RST_3") (pintype "passive"))
    )
    (net (code "94") (name "unconnected-(U2-RX-Pad42)") (class "Default")
      (node (ref "U2") (pin "42") (pinfunction "RX_42") (pintype "passive"))
    )
    (net (code "95") (name "unconnected-(U2-TX-Pad43)") (class "Default")
      (node (ref "U2") (pin "43") (pinfunction "TX_43") (pintype "passive"))
    )
    (net (code "96") (name "unconnected-(U3-N.C._1-Pad5)") (class "Default")
      (node (ref "U3") (pin "5") (pinfunction "N.C._1_5") (pintype "passive"))
    )
    (net (code "97") (name "unconnected-(U3-N.C._2-Pad6)") (class "Default")
      (node (ref "U3") (pin "6") (pinfunction "N.C._2_6") (pintype "passive"))
    )
    (net (code "98") (name "unconnected-(U3-N.C._3-Pad7)") (class "Default")
      (node (ref "U3") (pin "7") (pinfunction "N.C._3_7") (pintype "passive"))
    )
    (net (code "99") (name "unconnected-(U3-N.C._4-Pad8)") (class "Default")
      (node (ref "U3") (pin "8") (pinfunction "N.C._4_8") (pintype "passive"))
    )
    (net (code "100") (name "unconnected-(U3-N.C._5-Pad9)") (class "Default")
      (node (ref "U3") (pin "9") (pinfunction "N.C._5_9") (pintype "passive"))
    )
    (net (code "101") (name "unconnected-(U3-N.C._6-Pad10)") (class "Default")
      (node (ref "U3") (pin "10") (pinfunction "N.C._6_10") (pintype "passive"))
    )
    (net (code "102") (name "unconnected-(U3-N.C._7-Pad11)") (class "Default")
      (node (ref "U3") (pin "11") (pinfunction "N.C._7_11") (pintype "passive"))
    )
    (net (code "103") (name "unconnected-(U3-N.C._8-Pad12)") (class "Default")
      (node (ref "U3") (pin "12") (pinfunction "N.C._8_12") (pintype "passive"))
    )
    (net (code "104") (name "unconnected-(U4-ADKEY1-Pad12)") (class "Default")
      (node (ref "U4") (pin "12") (pinfunction "ADKEY1_12") (pintype "passive"))
    )
    (net (code "105") (name "unconnected-(U4-ADKEY2-Pad13)") (class "Default")
      (node (ref "U4") (pin "13") (pinfunction "ADKEY2_13") (pintype "passive"))
    )
    (net (code "106") (name "unconnected-(U4-DAC_L-Pad5)") (class "Default")
      (node (ref "U4") (pin "5") (pinfunction "DAC_L_5") (pintype "passive"))
    )
    (net (code "107") (name "unconnected-(U4-DAC_R-Pad4)") (class "Default")
      (node (ref "U4") (pin "4") (pinfunction "DAC_R_4") (pintype "passive"))
    )
    (net (code "108") (name "unconnected-(U4-IO1-Pad9)") (class "Default")
      (node (ref "U4") (pin "9") (pinfunction "IO1_9") (pintype "passive"))
    )
    (net (code "109") (name "unconnected-(U4-IO2-Pad11)") (class "Default")
      (node (ref "U4") (pin "11") (pinfunction "IO2_11") (pintype "passive"))
    )
    (net (code "110") (name "unconnected-(U4-USB+-Pad14)") (class "Default")
      (node (ref "U4") (pin "14") (pinfunction "USB+_14") (pintype "passive"))
    )
    (net (code "111") (name "unconnected-(U4-USB--Pad15)") (class "Default")
      (node (ref "U4") (pin "15") (pinfunction "USB-_15") (pintype "passive"))
    )
    (net (code "112") (name "unconnected-(U6-Q1-Pad9)") (class "Default")
      (node (ref "U6") (pin "9") (pinfunction "Q1_9") (pintype "passive"))
    )
    (net (code "113") (name "unconnected-(U6-Q2-Pad7)") (class "Default")
      (node (ref "U6") (pin "7") (pinfunction "Q2_7") (pintype "passive"))
    )
    (net (code "114") (name "unconnected-(U6-Q3-Pad6)") (class "Default")
      (node (ref "U6") (pin "6") (pinfunction "Q3_6") (pintype "passive"))
    )
    (net (code "115") (name "unconnected-(U6-Q4-Pad5)") (class "Default")
      (node (ref "U6") (pin "5") (pinfunction "Q4_5") (pintype "passive"))
    )
    (net (code "116") (name "unconnected-(U6-Q5-Pad3)") (class "Default")
      (node (ref "U6") (pin "3") (pinfunction "Q5_3") (pintype "passive"))
    )
    (net (code "117") (name "unconnected-(U6-Q7-Pad4)") (class "Default")
      (node (ref "U6") (pin "4") (pinfunction "Q7_4") (pintype "passive"))
    )
    (net (code "118") (name "unconnected-(U6-Q8-Pad13)") (class "Default")
      (node (ref "U6") (pin "13") (pinfunction "Q8_13") (pintype "passive"))
    )
    (net (code "119") (name "unconnected-(U6-Q9-Pad12)") (class "Default")
      (node (ref "U6") (pin "12") (pinfunction "Q9_12") (pintype "passive"))
    )
    (net (code "120") (name "unconnected-(U6-Q10-Pad14)") (class "Default")
      (node (ref "U6") (pin "14") (pinfunction "Q10_14") (pintype "passive"))
    )
    (net (code "121") (name "unconnected-(U6-Q11-Pad15)") (class "Default")
      (node (ref "U6") (pin "15") (pinfunction "Q11_15") (pintype "passive"))
    )
    (net (code "122") (name "unconnected-(U6-Q12-Pad1)") (class "Default")
      (node (ref "U6") (pin "1") (pinfunction "Q12_1") (pintype "passive"))
    )
  )
)
